# Liniar_Power_Source.net
KiCad netlist of a schematic drawn in Altium Designer
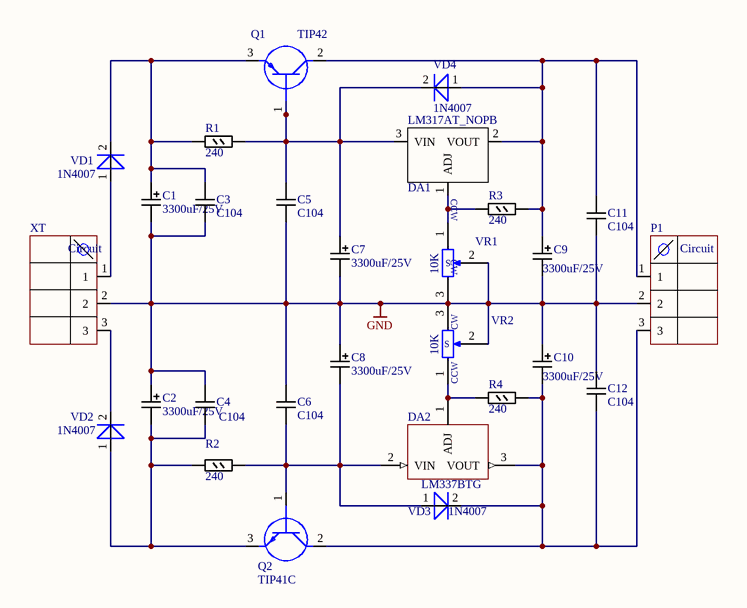
[diagram p0: Liniar Power Source.SchDoc]

(export (version "E")
  (design (tool "Eeschema 10.0.6"))
  (components
    (comp (ref "C1")
      (value "3300uF/25V")
      (footprint "Cap electrolitic radial 16x25 B")
      (fields (field (name "PART NUMBER") "Cap electrolitic radial 16x25"))
      (libsource (lib "SssAccesDatbase") (part "Cap Pol1"))
    )
    (comp (ref "C2")
      (value "3300uF/25V")
      (footprint "Cap electrolitic radial 16x25 B")
      (fields (field (name "PART NUMBER") "Cap electrolitic radial 16x25"))
      (libsource (lib "SssAccesDatbase") (part "Cap Pol1"))
    )
    (comp (ref "C3")
      (value "C104")
      (footprint "CAP CER 5x3x75mm")
      (fields (field (name "PART NUMBER") "CAP CER RADIAL"))
      (libsource (lib "SssAccesDatbase") (part "Cap"))
    )
    (comp (ref "C4")
      (value "C104")
      (footprint "CAP CER 5x3x75mm")
      (fields (field (name "PART NUMBER") "CAP CER RADIAL"))
      (libsource (lib "SssAccesDatbase") (part "Cap"))
    )
    (comp (ref "C5")
      (value "C104")
      (footprint "CAP CER 5x3x75mm")
      (fields (field (name "PART NUMBER") "CAP CER RADIAL"))
      (libsource (lib "SssAccesDatbase") (part "Cap"))
    )
    (comp (ref "C6")
      (value "C104")
      (footprint "CAP CER 5x3x75mm")
      (fields (field (name "PART NUMBER") "CAP CER RADIAL"))
      (libsource (lib "SssAccesDatbase") (part "Cap"))
    )
    (comp (ref "C7")
      (value "3300uF/25V")
      (footprint "Cap electrolitic radial 16x25 B")
      (fields (field (name "PART NUMBER") "Cap electrolitic radial 16x25"))
      (libsource (lib "SssAccesDatbase") (part "Cap Pol1"))
    )
    (comp (ref "C8")
      (value "3300uF/25V")
      (footprint "Cap electrolitic radial 16x25 B")
      (fields (field (name "PART NUMBER") "Cap electrolitic radial 16x25"))
      (libsource (lib "SssAccesDatbase") (part "Cap Pol1"))
    )
    (comp (ref "C9")
      (value "3300uF/25V")
      (footprint "Cap electrolitic radial 16x25 B")
      (fields (field (name "PART NUMBER") "Cap electrolitic radial 16x25"))
      (libsource (lib "SssAccesDatbase") (part "Cap Pol1"))
    )
    (comp (ref "C10")
      (value "3300uF/25V")
      (footprint "Cap electrolitic radial 16x25 B")
      (fields (field (name "PART NUMBER") "Cap electrolitic radial 16x25"))
      (libsource (lib "SssAccesDatbase") (part "Cap Pol1"))
    )
    (comp (ref "C11")
      (value "C104")
      (footprint "CAP CER 5x3x75mm")
      (fields (field (name "PART NUMBER") "CAP CER RADIAL"))
      (libsource (lib "SssAccesDatbase") (part "Cap"))
    )
    (comp (ref "C12")
      (value "C104")
      (footprint "CAP CER 5x3x75mm")
      (fields (field (name "PART NUMBER") "CAP CER RADIAL"))
      (libsource (lib "SssAccesDatbase") (part "Cap"))
    )
    (comp (ref "DA1")
      (value "LM317AT_NOPB")
      (footprint "TO254P470X1028X1955-3P")
      (description "Integrated Circuit")
      (fields
        (field (name "MANUFACTURER_PART_NUMBER") "LM317AT/NOPB")
        (field (name "MOUSER PART NUMBER") "926-LM317AT/NOPB")
      )
      (libsource (lib "AltiumDabaseLib") (part "LM317AT_NOPB"))
    )
    (comp (ref "DA2")
      (value "LM337BTG")
      (footprint "TO254P482X997X2018-3P")
      (description "Integrated Circuit")
      (fields (field (name "MOUSER PART NUMBER") "863-LM337BTG"))
      (libsource (lib "AltiumDabaseLib") (part "LM337BTG"))
    )
    (comp (ref "P1")
      (value "DG350-3.5-3")
      (footprint "DG350-3.5-3")
      (libsource (lib "SssAccesDatbase") (part "XT-3"))
    )
    (comp (ref "Q1")
      (value "TIP42")
      (footprint "SamacSys:TO254P483X1010X2035-3P")
      (description "Transistor BJT PNP")
      (fields (field (name "MOUSER PART NUMBER") "512-TIP42"))
      (libsource (lib "*") (part "TIP42"))
    )
    (comp (ref "Q2")
      (value "TIP41C")
      (footprint "SamacSys:TO254P483X1010X2035-3P")
      (description "Transistor BJT NPN")
      (fields (field (name "MOUSER PART NUMBER") "512-TIP41C"))
      (libsource (lib "*") (part "TIP41C"))
    )
    (comp (ref "R1")
      (value "240")
      (footprint "RESC2012(0805)N")
      (fields (field (name "PART NUMBER") "RESC2012(0805)"))
      (libsource (lib "SssAccesDatbase") (part "Resistor 0,125W"))
    )
    (comp (ref "R2")
      (value "240")
      (footprint "RESC2012(0805)N")
      (fields (field (name "PART NUMBER") "RESC2012(0805)"))
      (libsource (lib "SssAccesDatbase") (part "Resistor 0,125W"))
    )
    (comp (ref "R3")
      (value "240")
      (footprint "RESC2012(0805)N")
      (fields (field (name "PART NUMBER") "RESC2012(0805)"))
      (libsource (lib "SssAccesDatbase") (part "Resistor 0,125W"))
    )
    (comp (ref "R4")
      (value "240")
      (footprint "RESC2012(0805)N")
      (fields (field (name "PART NUMBER") "RESC2012(0805)"))
      (libsource (lib "SssAccesDatbase") (part "Resistor 0,125W"))
    )
    (comp (ref "VD1")
      (value "1N4007")
      (footprint "DO-35")
      (description "Small Signal Diode")
      (fields (field (name "PART NUMBER") "1N4148"))
      (libsource (lib "SssAccesDatbase") (part "Diode_1_2"))
    )
    (comp (ref "VD2")
      (value "1N4007")
      (footprint "DO-35")
      (description "Small Signal Diode")
      (fields (field (name "PART NUMBER") "1N4148"))
      (libsource (lib "SssAccesDatbase") (part "Diode_1_2"))
    )
    (comp (ref "VD3")
      (value "1N4007")
      (footprint "DO-35")
      (description "Small Signal Diode")
      (fields (field (name "PART NUMBER") "1N4148"))
      (libsource (lib "SssAccesDatbase") (part "Diode_1_2"))
    )
    (comp (ref "VD4")
      (value "1N4007")
      (footprint "DO-35")
      (description "Small Signal Diode")
      (fields (field (name "PART NUMBER") "1N4148"))
      (libsource (lib "SssAccesDatbase") (part "Diode_1_2"))
    )
    (comp (ref "VR1")
      (value "10K")
      (footprint "P160KN0QC15B50K")
      (description "Variable Resistor")
      (fields
        (field (name "MANUFACTURER_PART_NUMBER") "P160KN-0QC15B50K")
        (field (name "MOUSER PART NUMBER") "858-P160KN-0QC15B50K")
      )
      (libsource (lib "") (part "P160KN-0QC15B50K_1"))
    )
    (comp (ref "VR2")
      (value "10K")
      (footprint "P160KN0QC15B50K")
      (description "Variable Resistor")
      (fields
        (field (name "MANUFACTURER_PART_NUMBER") "P160KN-0QC15B50K")
        (field (name "MOUSER PART NUMBER") "858-P160KN-0QC15B50K")
      )
      (libsource (lib "AltiumDabaseLib") (part "P160KN-0QC15B50K"))
    )
    (comp (ref "XT") (value "DG350-3.5-3") (footprint "DG350-3.5-3") (libsource (lib "") (part "XT-3_1")))
  )
  (nets
    (net (code "1") (name "GND") (class "Default")
      (node (ref "C1") (pin "2") (pinfunction "2_2") (pintype "passive"))
      (node (ref "C10") (pin "1") (pinfunction "1_1") (pintype "passive"))
      (node (ref "C11") (pin "1") (pinfunction "1_1") (pintype "passive"))
      (node (ref "C12") (pin "2") (pinfunction "2_2") (pintype "passive"))
      (node (ref "C2") (pin "1") (pinfunction "1_1") (pintype "passive"))
      (node (ref "C3") (pin "1") (pinfunction "1_1") (pintype "passive"))
      (node (ref "C4") (pin "2") (pinfunction "2_2") (pintype "passive"))
      (node (ref "C5") (pin "1") (pinfunction "1_1") (pintype "passive"))
      (node (ref "C6") (pin "2") (pinfunction "2_2") (pintype "passive"))
      (node (ref "C7") (pin "2") (pinfunction "2_2") (pintype "passive"))
      (node (ref "C8") (pin "1") (pinfunction "1_1") (pintype "passive"))
      (node (ref "C9") (pin "2") (pinfunction "2_2") (pintype "passive"))
      (node (ref "P1") (pin "2") (pinfunction "2_2") (pintype "passive"))
      (node (ref "VR1") (pin "3") (pinfunction "CW_3") (pintype "passive"))
      (node (ref "VR2") (pin "3") (pinfunction "CW_3") (pintype "passive"))
      (node (ref "XT") (pin "2") (pinfunction "2_2") (pintype "passive"))
    )
    (net (code "2") (name "Net-(DA1-ADJ)") (class "Default")
      (node (ref "DA1") (pin "1") (pinfunction "ADJ_1") (pintype "passive"))
      (node (ref "R3") (pin "1") (pinfunction "1_1") (pintype "passive"))
      (node (ref "VR1") (pin "1") (pinfunction "CCW_1") (pintype "passive"))
    )
    (net (code "3") (name "Net-(DA1-VIN)") (class "Default")
      (node (ref "C5") (pin "2") (pinfunction "2_2") (pintype "passive"))
      (node (ref "C7") (pin "1") (pinfunction "1_1") (pintype "passive"))
      (node (ref "DA1") (pin "3") (pinfunction "VIN_3") (pintype "passive"))
      (node (ref "Q1") (pin "1") (pinfunction "B_1") (pintype "passive"))
      (node (ref "R1") (pin "2") (pinfunction "2_2") (pintype "passive"))
      (node (ref "VD4") (pin "2") (pintype "passive"))
    )
    (net (code "4") (name "Net-(DA1-VOUT)") (class "Default")
      (node (ref "C11") (pin "2") (pinfunction "2_2") (pintype "passive"))
      (node (ref "C9") (pin "1") (pinfunction "1_1") (pintype "passive"))
      (node (ref "DA1") (pin "2") (pinfunction "VOUT_2") (pintype "passive"))
      (node (ref "P1") (pin "1") (pinfunction "1_1") (pintype "passive"))
      (node (ref "Q1") (pin "2") (pinfunction "C_2") (pintype "passive"))
      (node (ref "R3") (pin "2") (pinfunction "2_2") (pintype "passive"))
      (node (ref "VD4") (pin "1") (pintype "passive"))
    )
    (net (code "5") (name "Net-(DA2-ADJ)") (class "Default")
      (node (ref "DA2") (pin "1") (pinfunction "ADJ_1") (pintype "passive"))
      (node (ref "R4") (pin "1") (pinfunction "1_1") (pintype "passive"))
      (node (ref "VR2") (pin "1") (pinfunction "CCW_1") (pintype "passive"))
    )
    (net (code "6") (name "Net-(DA2-VIN)") (class "Default")
      (node (ref "C6") (pin "1") (pinfunction "1_1") (pintype "passive"))
      (node (ref "C8") (pin "2") (pinfunction "2_2") (pintype "passive"))
      (node (ref "DA2") (pin "2") (pinfunction "VIN_2") (pintype "input"))
      (node (ref "Q2") (pin "1") (pinfunction "B_1") (pintype "passive"))
      (node (ref "R2") (pin "2") (pinfunction "2_2") (pintype "passive"))
      (node (ref "VD3") (pin "1") (pintype "passive"))
    )
    (net (code "7") (name "Net-(DA2-VOUT)") (class "Default")
      (node (ref "C10") (pin "2") (pinfunction "2_2") (pintype "passive"))
      (node (ref "C12") (pin "1") (pinfunction "1_1") (pintype "passive"))
      (node (ref "DA2") (pin "3") (pinfunction "VOUT_3") (pintype "output"))
      (node (ref "P1") (pin "3") (pinfunction "3_3") (pintype "passive"))
      (node (ref "Q2") (pin "2") (pinfunction "C_2") (pintype "passive"))
      (node (ref "R4") (pin "2") (pinfunction "2_2") (pintype "passive"))
      (node (ref "VD3") (pin "2") (pintype "passive"))
    )
    (net (code "8") (name "Net-(Q1-E)") (class "Default")
      (node (ref "C1") (pin "1") (pinfunction "1_1") (pintype "passive"))
      (node (ref "C3") (pin "2") (pinfunction "2_2") (pintype "passive"))
      (node (ref "Q1") (pin "3") (pinfunction "E_3") (pintype "passive"))
      (node (ref "R1") (pin "1") (pinfunction "1_1") (pintype "passive"))
      (node (ref "VD1") (pin "2") (pintype "passive"))
    )
    (net (code "9") (name "Net-(Q2-E)") (class "Default")
      (node (ref "C2") (pin "2") (pinfunction "2_2") (pintype "passive"))
      (node (ref "C4") (pin "1") (pinfunction "1_1") (pintype "passive"))
      (node (ref "Q2") (pin "3") (pinfunction "E_3") (pintype "passive"))
      (node (ref "R2") (pin "1") (pinfunction "1_1") (pintype "passive"))
      (node (ref "VD2") (pin "1") (pintype "passive"))
    )
    (net (code "10") (name "Net-(VD1-Pad1)") (class "Default")
      (node (ref "VD1") (pin "1") (pintype "passive"))
      (node (ref "XT") (pin "1") (pinfunction "1_1") (pintype "passive"))
    )
    (net (code "11") (name "Net-(VD2-Pad2)") (class "Default")
      (node (ref "VD2") (pin "2") (pintype "passive"))
      (node (ref "XT") (pin "3") (pinfunction "3_3") (pintype "passive"))
    )
    (net (code "12") (name "unconnected-(VR1-S-Pad2)") (class "Default")
      (node (ref "VR1") (pin "2") (pinfunction "S_2") (pintype "passive"))
    )
    (net (code "13") (name "unconnected-(VR2-S-Pad2)") (class "Default")
      (node (ref "VR2") (pin "2") (pinfunction "S_2") (pintype "passive"))
    )
  )
)
